# Pros_touch_weight_sensor-v1_0_0-2023-4-8.net
KiCad netlist of a schematic drawn in EasyEDA Pro
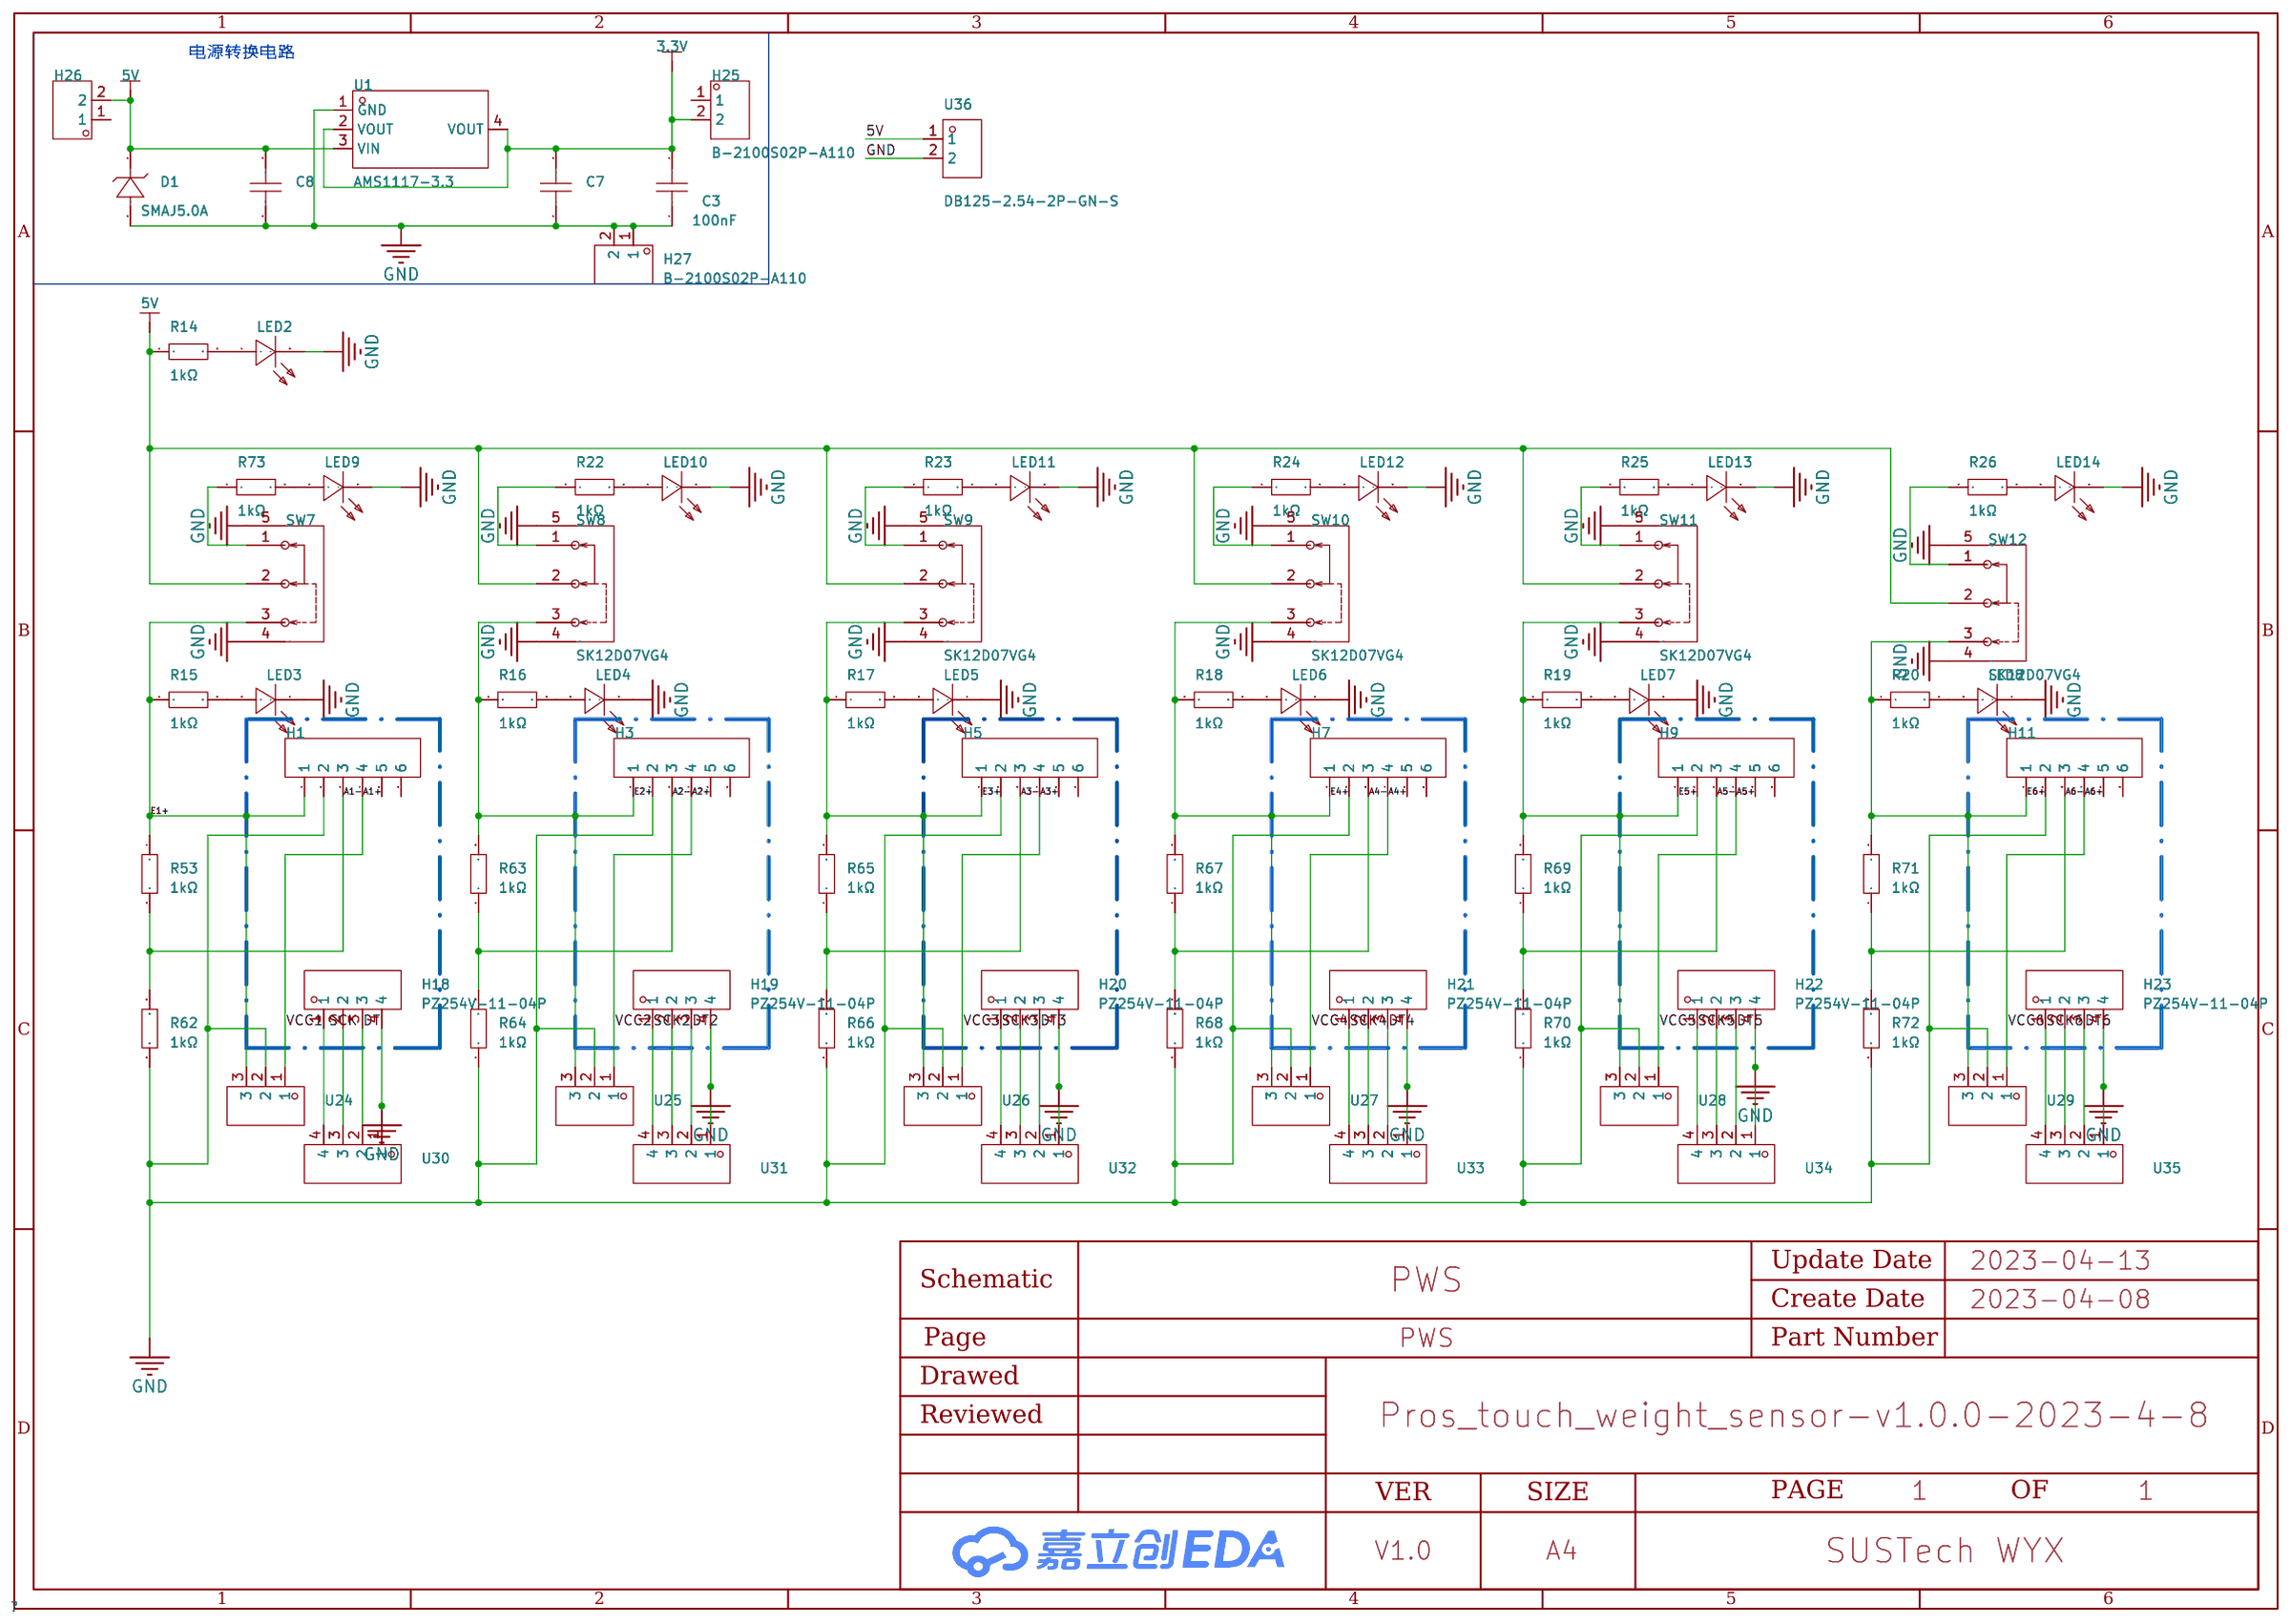
[diagram p0: schematic sheet]

(export (version "E")
  (design (tool "Eeschema 10.0.6"))
  (components
    (comp (ref "C3")
      (value "100nF")
      (footprint "easyedapro:C0603")
      (description "容值:100nF;精度:±10%;额定电压:50V;材质(温度系数):X7R;")
      (fields
        (field (name "Manufacturer Part") "CC0603KRX7R9BB104")
        (field (name "Manufacturer") "YAGEO(国巨)")
      )
      (libsource (lib "easyedapro") (part "CC0603KRX7R9BB104"))
    )
    (comp (ref "C7")
      (value "GRM31CC80J476KE01L")
      (footprint "easyedapro:C1206")
      (fields (field (name "Manufacturer") "muRata(村田)"))
      (libsource (lib "easyedapro") (part "GRM31CC80J476KE01L"))
    )
    (comp (ref "C8")
      (value "GRM31CC80J476KE01L")
      (footprint "easyedapro:C1206")
      (fields (field (name "Manufacturer") "muRata(村田)"))
      (libsource (lib "easyedapro") (part "GRM31CC80J476KE01L"))
    )
    (comp (ref "D1")
      (value "SMAJ5.0A")
      (footprint "easyedapro:SMA_L4.3-W2.6-LS5.0-RD")
      (fields (field (name "Manufacturer") "FUXINSEMI(富芯森美)"))
      (libsource (lib "easyedapro") (part "SMAJ5.0A_C908198"))
    )
    (comp (ref "H1")
      (value "2.54-1x6P直针")
      (footprint "easyedapro:HDR-TH_6P-P2.54-V-M-1")
      (fields (field (name "Manufacturer") "BOOMELE(博穆精密)"))
      (libsource (lib "easyedapro") (part "Header-Male-2.54_1x6"))
    )
    (comp (ref "H3")
      (value "2.54-1x6P直针")
      (footprint "easyedapro:HDR-TH_6P-P2.54-V-M-1")
      (fields (field (name "Manufacturer") "BOOMELE(博穆精密)"))
      (libsource (lib "easyedapro") (part "Header-Male-2.54_1x6"))
    )
    (comp (ref "H5")
      (value "2.54-1x6P直针")
      (footprint "easyedapro:HDR-TH_6P-P2.54-V-M-1")
      (fields (field (name "Manufacturer") "BOOMELE(博穆精密)"))
      (libsource (lib "easyedapro") (part "Header-Male-2.54_1x6"))
    )
    (comp (ref "H7")
      (value "2.54-1x6P直针")
      (footprint "easyedapro:HDR-TH_6P-P2.54-V-M-1")
      (fields (field (name "Manufacturer") "BOOMELE(博穆精密)"))
      (libsource (lib "easyedapro") (part "Header-Male-2.54_1x6"))
    )
    (comp (ref "H9")
      (value "2.54-1x6P直针")
      (footprint "easyedapro:HDR-TH_6P-P2.54-V-M-1")
      (fields (field (name "Manufacturer") "BOOMELE(博穆精密)"))
      (libsource (lib "easyedapro") (part "Header-Male-2.54_1x6"))
    )
    (comp (ref "H11")
      (value "2.54-1x6P直针")
      (footprint "easyedapro:HDR-TH_6P-P2.54-V-M-1")
      (fields (field (name "Manufacturer") "BOOMELE(博穆精密)"))
      (libsource (lib "easyedapro") (part "Header-Male-2.54_1x6"))
    )
    (comp (ref "H18")
      (value "PZ254V-11-04P")
      (footprint "easyedapro:HDR-TH_4P-P2.54-V-M")
      (fields (field (name "Manufacturer") "XFCN(兴飞)"))
      (libsource (lib "easyedapro") (part "PZ254V-11-04P_C2691448"))
    )
    (comp (ref "H19")
      (value "PZ254V-11-04P")
      (footprint "easyedapro:HDR-TH_4P-P2.54-V-M")
      (fields (field (name "Manufacturer") "XFCN(兴飞)"))
      (libsource (lib "easyedapro") (part "PZ254V-11-04P_C2691448"))
    )
    (comp (ref "H20")
      (value "PZ254V-11-04P")
      (footprint "easyedapro:HDR-TH_4P-P2.54-V-M")
      (fields (field (name "Manufacturer") "XFCN(兴飞)"))
      (libsource (lib "easyedapro") (part "PZ254V-11-04P_C2691448"))
    )
    (comp (ref "H21")
      (value "PZ254V-11-04P")
      (footprint "easyedapro:HDR-TH_4P-P2.54-V-M")
      (fields (field (name "Manufacturer") "XFCN(兴飞)"))
      (libsource (lib "easyedapro") (part "PZ254V-11-04P_C2691448"))
    )
    (comp (ref "H22")
      (value "PZ254V-11-04P")
      (footprint "easyedapro:HDR-TH_4P-P2.54-V-M")
      (fields (field (name "Manufacturer") "XFCN(兴飞)"))
      (libsource (lib "easyedapro") (part "PZ254V-11-04P_C2691448"))
    )
    (comp (ref "H23")
      (value "PZ254V-11-04P")
      (footprint "easyedapro:HDR-TH_4P-P2.54-V-M")
      (fields (field (name "Manufacturer") "XFCN(兴飞)"))
      (libsource (lib "easyedapro") (part "PZ254V-11-04P_C2691448"))
    )
    (comp (ref "H25")
      (value "B-2100S02P-A110")
      (footprint "easyedapro:HDR-TH_2P-P2.54-V-M-1")
      (fields (field (name "Manufacturer") "Ckmtw(灿科盟)"))
      (libsource (lib "easyedapro") (part "210S-1*2P L=11.6MMGold-plated black"))
    )
    (comp (ref "H26")
      (value "B-2100S02P-A110")
      (footprint "easyedapro:HDR-TH_2P-P2.54-V-M-1")
      (fields (field (name "Manufacturer") "Ckmtw(灿科盟)"))
      (libsource (lib "easyedapro") (part "210S-1*2P L=11.6MMGold-plated black"))
    )
    (comp (ref "H27")
      (value "B-2100S02P-A110")
      (footprint "easyedapro:HDR-TH_2P-P2.54-V-M-1")
      (fields (field (name "Manufacturer") "Ckmtw(灿科盟)"))
      (libsource (lib "easyedapro") (part "210S-1*2P L=11.6MMGold-plated black"))
    )
    (comp (ref "LED2")
      (value "NCD0805B2")
      (footprint "easyedapro:LED0805-RD")
      (description "照明颜色:蓝色;主波长/色坐标:468~478nm;")
      (fields (field (name "Manufacturer") "国星光电"))
      (libsource (lib "easyedapro") (part "FC-A2012BK-470H2"))
    )
    (comp (ref "LED3")
      (value "NCD1206G1")
      (footprint "easyedapro:LED1206-RD")
      (description "照明颜色:翠绿;色温 - CCT（K）:-;主波长/色坐标:525~530nm;")
      (fields (field (name "Manufacturer") "国星光电"))
      (libsource (lib "easyedapro") (part "FC-3215UGK-520D"))
    )
    (comp (ref "LED4")
      (value "NCD1206G1")
      (footprint "easyedapro:LED1206-RD")
      (description "照明颜色:翠绿;色温 - CCT（K）:-;主波长/色坐标:525~530nm;")
      (fields (field (name "Manufacturer") "国星光电"))
      (libsource (lib "easyedapro") (part "FC-3215UGK-520D"))
    )
    (comp (ref "LED5")
      (value "NCD1206G1")
      (footprint "easyedapro:LED1206-RD")
      (description "照明颜色:翠绿;色温 - CCT（K）:-;主波长/色坐标:525~530nm;")
      (fields (field (name "Manufacturer") "国星光电"))
      (libsource (lib "easyedapro") (part "FC-3215UGK-520D"))
    )
    (comp (ref "LED6")
      (value "NCD1206G1")
      (footprint "easyedapro:LED1206-RD")
      (description "照明颜色:翠绿;色温 - CCT（K）:-;主波长/色坐标:525~530nm;")
      (fields (field (name "Manufacturer") "国星光电"))
      (libsource (lib "easyedapro") (part "FC-3215UGK-520D"))
    )
    (comp (ref "LED7")
      (value "NCD1206G1")
      (footprint "easyedapro:LED1206-RD")
      (description "照明颜色:翠绿;色温 - CCT（K）:-;主波长/色坐标:525~530nm;")
      (fields (field (name "Manufacturer") "国星光电"))
      (libsource (lib "easyedapro") (part "FC-3215UGK-520D"))
    )
    (comp (ref "LED8")
      (value "NCD1206G1")
      (footprint "easyedapro:LED1206-RD")
      (description "照明颜色:翠绿;色温 - CCT（K）:-;主波长/色坐标:525~530nm;")
      (fields (field (name "Manufacturer") "国星光电"))
      (libsource (lib "easyedapro") (part "FC-3215UGK-520D"))
    )
    (comp (ref "LED9")
      (value "NCD0805B2")
      (footprint "easyedapro:LED0805-RD")
      (description "照明颜色:蓝色;主波长/色坐标:468~478nm;")
      (fields (field (name "Manufacturer") "国星光电"))
      (libsource (lib "easyedapro") (part "FC-A2012BK-470H2"))
    )
    (comp (ref "LED10")
      (value "NCD0805B2")
      (footprint "easyedapro:LED0805-RD")
      (description "照明颜色:蓝色;主波长/色坐标:468~478nm;")
      (fields (field (name "Manufacturer") "国星光电"))
      (libsource (lib "easyedapro") (part "FC-A2012BK-470H2"))
    )
    (comp (ref "LED11")
      (value "NCD0805B2")
      (footprint "easyedapro:LED0805-RD")
      (description "照明颜色:蓝色;主波长/色坐标:468~478nm;")
      (fields (field (name "Manufacturer") "国星光电"))
      (libsource (lib "easyedapro") (part "FC-A2012BK-470H2"))
    )
    (comp (ref "LED12")
      (value "NCD0805B2")
      (footprint "easyedapro:LED0805-RD")
      (description "照明颜色:蓝色;主波长/色坐标:468~478nm;")
      (fields (field (name "Manufacturer") "国星光电"))
      (libsource (lib "easyedapro") (part "FC-A2012BK-470H2"))
    )
    (comp (ref "LED13")
      (value "NCD0805B2")
      (footprint "easyedapro:LED0805-RD")
      (description "照明颜色:蓝色;主波长/色坐标:468~478nm;")
      (fields (field (name "Manufacturer") "国星光电"))
      (libsource (lib "easyedapro") (part "FC-A2012BK-470H2"))
    )
    (comp (ref "LED14")
      (value "NCD0805B2")
      (footprint "easyedapro:LED0805-RD")
      (description "照明颜色:蓝色;主波长/色坐标:468~478nm;")
      (fields (field (name "Manufacturer") "国星光电"))
      (libsource (lib "easyedapro") (part "FC-A2012BK-470H2"))
    )
    (comp (ref "R14")
      (value "1kΩ")
      (footprint "easyedapro:R0603")
      (description "电阻类型:厚膜电阻;阻值:1kΩ;精度:±1%;功率:1/10W;温度系数:±100ppm/°C;最大工作电压:75V;工作温度范围:-55°C~+155°C;")
      (fields
        (field (name "Manufacturer Part") "0603WAF1001T5E")
        (field (name "Manufacturer") "UNI-ROYAL(厚声)")
      )
      (libsource (lib "easyedapro") (part "0603WAF1001T5E"))
    )
    (comp (ref "R15")
      (value "1kΩ")
      (footprint "easyedapro:R0603")
      (description "电阻类型:厚膜电阻;阻值:1kΩ;精度:±1%;功率:1/10W;温度系数:±100ppm/°C;最大工作电压:75V;工作温度范围:-55°C~+155°C;")
      (fields
        (field (name "Manufacturer Part") "0603WAF1001T5E")
        (field (name "Manufacturer") "UNI-ROYAL(厚声)")
      )
      (libsource (lib "easyedapro") (part "0603WAF1001T5E"))
    )
    (comp (ref "R16")
      (value "1kΩ")
      (footprint "easyedapro:R0603")
      (description "电阻类型:厚膜电阻;阻值:1kΩ;精度:±1%;功率:1/10W;温度系数:±100ppm/°C;最大工作电压:75V;工作温度范围:-55°C~+155°C;")
      (fields
        (field (name "Manufacturer Part") "0603WAF1001T5E")
        (field (name "Manufacturer") "UNI-ROYAL(厚声)")
      )
      (libsource (lib "easyedapro") (part "0603WAF1001T5E"))
    )
    (comp (ref "R17")
      (value "1kΩ")
      (footprint "easyedapro:R0603")
      (description "电阻类型:厚膜电阻;阻值:1kΩ;精度:±1%;功率:1/10W;温度系数:±100ppm/°C;最大工作电压:75V;工作温度范围:-55°C~+155°C;")
      (fields
        (field (name "Manufacturer Part") "0603WAF1001T5E")
        (field (name "Manufacturer") "UNI-ROYAL(厚声)")
      )
      (libsource (lib "easyedapro") (part "0603WAF1001T5E"))
    )
    (comp (ref "R18")
      (value "1kΩ")
      (footprint "easyedapro:R0603")
      (description "电阻类型:厚膜电阻;阻值:1kΩ;精度:±1%;功率:1/10W;温度系数:±100ppm/°C;最大工作电压:75V;工作温度范围:-55°C~+155°C;")
      (fields
        (field (name "Manufacturer Part") "0603WAF1001T5E")
        (field (name "Manufacturer") "UNI-ROYAL(厚声)")
      )
      (libsource (lib "easyedapro") (part "0603WAF1001T5E"))
    )
    (comp (ref "R19")
      (value "1kΩ")
      (footprint "easyedapro:R0603")
      (description "电阻类型:厚膜电阻;阻值:1kΩ;精度:±1%;功率:1/10W;温度系数:±100ppm/°C;最大工作电压:75V;工作温度范围:-55°C~+155°C;")
      (fields
        (field (name "Manufacturer Part") "0603WAF1001T5E")
        (field (name "Manufacturer") "UNI-ROYAL(厚声)")
      )
      (libsource (lib "easyedapro") (part "0603WAF1001T5E"))
    )
    (comp (ref "R20")
      (value "1kΩ")
      (footprint "easyedapro:R0603")
      (description "电阻类型:厚膜电阻;阻值:1kΩ;精度:±1%;功率:1/10W;温度系数:±100ppm/°C;最大工作电压:75V;工作温度范围:-55°C~+155°C;")
      (fields
        (field (name "Manufacturer Part") "0603WAF1001T5E")
        (field (name "Manufacturer") "UNI-ROYAL(厚声)")
      )
      (libsource (lib "easyedapro") (part "0603WAF1001T5E"))
    )
    (comp (ref "R22")
      (value "1kΩ")
      (footprint "easyedapro:R0603")
      (description "电阻类型:厚膜电阻;阻值:1kΩ;精度:±1%;功率:1/10W;温度系数:±100ppm/°C;最大工作电压:75V;工作温度范围:-55°C~+155°C;")
      (fields
        (field (name "Manufacturer Part") "0603WAF1001T5E")
        (field (name "Manufacturer") "UNI-ROYAL(厚声)")
      )
      (libsource (lib "easyedapro") (part "0603WAF1001T5E"))
    )
    (comp (ref "R23")
      (value "1kΩ")
      (footprint "easyedapro:R0603")
      (description "电阻类型:厚膜电阻;阻值:1kΩ;精度:±1%;功率:1/10W;温度系数:±100ppm/°C;最大工作电压:75V;工作温度范围:-55°C~+155°C;")
      (fields
        (field (name "Manufacturer Part") "0603WAF1001T5E")
        (field (name "Manufacturer") "UNI-ROYAL(厚声)")
      )
      (libsource (lib "easyedapro") (part "0603WAF1001T5E"))
    )
    (comp (ref "R24")
      (value "1kΩ")
      (footprint "easyedapro:R0603")
      (description "电阻类型:厚膜电阻;阻值:1kΩ;精度:±1%;功率:1/10W;温度系数:±100ppm/°C;最大工作电压:75V;工作温度范围:-55°C~+155°C;")
      (fields
        (field (name "Manufacturer Part") "0603WAF1001T5E")
        (field (name "Manufacturer") "UNI-ROYAL(厚声)")
      )
      (libsource (lib "easyedapro") (part "0603WAF1001T5E"))
    )
    (comp (ref "R25")
      (value "1kΩ")
      (footprint "easyedapro:R0603")
      (description "电阻类型:厚膜电阻;阻值:1kΩ;精度:±1%;功率:1/10W;温度系数:±100ppm/°C;最大工作电压:75V;工作温度范围:-55°C~+155°C;")
      (fields
        (field (name "Manufacturer Part") "0603WAF1001T5E")
        (field (name "Manufacturer") "UNI-ROYAL(厚声)")
      )
      (libsource (lib "easyedapro") (part "0603WAF1001T5E"))
    )
    (comp (ref "R26")
      (value "1kΩ")
      (footprint "easyedapro:R0603")
      (description "电阻类型:厚膜电阻;阻值:1kΩ;精度:±1%;功率:1/10W;温度系数:±100ppm/°C;最大工作电压:75V;工作温度范围:-55°C~+155°C;")
      (fields
        (field (name "Manufacturer Part") "0603WAF1001T5E")
        (field (name "Manufacturer") "UNI-ROYAL(厚声)")
      )
      (libsource (lib "easyedapro") (part "0603WAF1001T5E"))
    )
    (comp (ref "R53")
      (value "1kΩ")
      (footprint "easyedapro:R0402")
      (description "电阻类型:薄膜电阻;阻值:1kΩ;精度:±0.1%;功率:63mW;温度系数:±25ppm/K;最大工作电压:50V;工作温度范围:-55°C~+155°C;")
      (fields (field (name "Manufacturer Part") "ERA2AEB102X") (field (name "Manufacturer") "PANASONIC(松下)"))
      (libsource (lib "easyedapro") (part "ERA2AEB102X"))
    )
    (comp (ref "R62")
      (value "1kΩ")
      (footprint "easyedapro:R0402")
      (description "电阻类型:薄膜电阻;阻值:1kΩ;精度:±0.1%;功率:63mW;温度系数:±25ppm/K;最大工作电压:50V;工作温度范围:-55°C~+155°C;")
      (fields (field (name "Manufacturer Part") "ERA2AEB102X") (field (name "Manufacturer") "PANASONIC(松下)"))
      (libsource (lib "easyedapro") (part "ERA2AEB102X"))
    )
    (comp (ref "R63")
      (value "1kΩ")
      (footprint "easyedapro:R0402")
      (description "电阻类型:薄膜电阻;阻值:1kΩ;精度:±0.1%;功率:63mW;温度系数:±25ppm/K;最大工作电压:50V;工作温度范围:-55°C~+155°C;")
      (fields (field (name "Manufacturer Part") "ERA2AEB102X") (field (name "Manufacturer") "PANASONIC(松下)"))
      (libsource (lib "easyedapro") (part "ERA2AEB102X"))
    )
    (comp (ref "R64")
      (value "1kΩ")
      (footprint "easyedapro:R0402")
      (description "电阻类型:薄膜电阻;阻值:1kΩ;精度:±0.1%;功率:63mW;温度系数:±25ppm/K;最大工作电压:50V;工作温度范围:-55°C~+155°C;")
      (fields (field (name "Manufacturer Part") "ERA2AEB102X") (field (name "Manufacturer") "PANASONIC(松下)"))
      (libsource (lib "easyedapro") (part "ERA2AEB102X"))
    )
    (comp (ref "R65")
      (value "1kΩ")
      (footprint "easyedapro:R0402")
      (description "电阻类型:薄膜电阻;阻值:1kΩ;精度:±0.1%;功率:63mW;温度系数:±25ppm/K;最大工作电压:50V;工作温度范围:-55°C~+155°C;")
      (fields (field (name "Manufacturer Part") "ERA2AEB102X") (field (name "Manufacturer") "PANASONIC(松下)"))
      (libsource (lib "easyedapro") (part "ERA2AEB102X"))
    )
    (comp (ref "R66")
      (value "1kΩ")
      (footprint "easyedapro:R0402")
      (description "电阻类型:薄膜电阻;阻值:1kΩ;精度:±0.1%;功率:63mW;温度系数:±25ppm/K;最大工作电压:50V;工作温度范围:-55°C~+155°C;")
      (fields (field (name "Manufacturer Part") "ERA2AEB102X") (field (name "Manufacturer") "PANASONIC(松下)"))
      (libsource (lib "easyedapro") (part "ERA2AEB102X"))
    )
    (comp (ref "R67")
      (value "1kΩ")
      (footprint "easyedapro:R0402")
      (description "电阻类型:薄膜电阻;阻值:1kΩ;精度:±0.1%;功率:63mW;温度系数:±25ppm/K;最大工作电压:50V;工作温度范围:-55°C~+155°C;")
      (fields (field (name "Manufacturer Part") "ERA2AEB102X") (field (name "Manufacturer") "PANASONIC(松下)"))
      (libsource (lib "easyedapro") (part "ERA2AEB102X"))
    )
    (comp (ref "R68")
      (value "1kΩ")
      (footprint "easyedapro:R0402")
      (description "电阻类型:薄膜电阻;阻值:1kΩ;精度:±0.1%;功率:63mW;温度系数:±25ppm/K;最大工作电压:50V;工作温度范围:-55°C~+155°C;")
      (fields (field (name "Manufacturer Part") "ERA2AEB102X") (field (name "Manufacturer") "PANASONIC(松下)"))
      (libsource (lib "easyedapro") (part "ERA2AEB102X"))
    )
    (comp (ref "R69")
      (value "1kΩ")
      (footprint "easyedapro:R0402")
      (description "电阻类型:薄膜电阻;阻值:1kΩ;精度:±0.1%;功率:63mW;温度系数:±25ppm/K;最大工作电压:50V;工作温度范围:-55°C~+155°C;")
      (fields (field (name "Manufacturer Part") "ERA2AEB102X") (field (name "Manufacturer") "PANASONIC(松下)"))
      (libsource (lib "easyedapro") (part "ERA2AEB102X"))
    )
    (comp (ref "R70")
      (value "1kΩ")
      (footprint "easyedapro:R0402")
      (description "电阻类型:薄膜电阻;阻值:1kΩ;精度:±0.1%;功率:63mW;温度系数:±25ppm/K;最大工作电压:50V;工作温度范围:-55°C~+155°C;")
      (fields (field (name "Manufacturer Part") "ERA2AEB102X") (field (name "Manufacturer") "PANASONIC(松下)"))
      (libsource (lib "easyedapro") (part "ERA2AEB102X"))
    )
    (comp (ref "R71")
      (value "1kΩ")
      (footprint "easyedapro:R0402")
      (description "电阻类型:薄膜电阻;阻值:1kΩ;精度:±0.1%;功率:63mW;温度系数:±25ppm/K;最大工作电压:50V;工作温度范围:-55°C~+155°C;")
      (fields (field (name "Manufacturer Part") "ERA2AEB102X") (field (name "Manufacturer") "PANASONIC(松下)"))
      (libsource (lib "easyedapro") (part "ERA2AEB102X"))
    )
    (comp (ref "R72")
      (value "1kΩ")
      (footprint "easyedapro:R0402")
      (description "电阻类型:薄膜电阻;阻值:1kΩ;精度:±0.1%;功率:63mW;温度系数:±25ppm/K;最大工作电压:50V;工作温度范围:-55°C~+155°C;")
      (fields (field (name "Manufacturer Part") "ERA2AEB102X") (field (name "Manufacturer") "PANASONIC(松下)"))
      (libsource (lib "easyedapro") (part "ERA2AEB102X"))
    )
    (comp (ref "R73")
      (value "1kΩ")
      (footprint "easyedapro:R0603")
      (description "电阻类型:厚膜电阻;阻值:1kΩ;精度:±1%;功率:1/10W;温度系数:±100ppm/°C;最大工作电压:75V;工作温度范围:-55°C~+155°C;")
      (fields
        (field (name "Manufacturer Part") "0603WAF1001T5E")
        (field (name "Manufacturer") "UNI-ROYAL(厚声)")
      )
      (libsource (lib "easyedapro") (part "0603WAF1001T5E"))
    )
    (comp (ref "SW7")
      (value "SK12D07VG4")
      (footprint "easyedapro:SW-TH_SK12D07VG4")
      (description "额定电压 DC:50V;触点额定电流:500mA @ 50VDC;电路结构:SPDT;额定电压 AC:-;开关功能:On-On;")
      (fields (field (name "Manufacturer") "SHOU HAN(首韩)"))
      (libsource (lib "easyedapro") (part "SK12D07VG4"))
    )
    (comp (ref "SW8")
      (value "SK12D07VG4")
      (footprint "easyedapro:SW-TH_SK12D07VG4")
      (description "额定电压 DC:50V;触点额定电流:500mA @ 50VDC;电路结构:SPDT;额定电压 AC:-;开关功能:On-On;")
      (fields (field (name "Manufacturer") "SHOU HAN(首韩)"))
      (libsource (lib "easyedapro") (part "SK12D07VG4"))
    )
    (comp (ref "SW9")
      (value "SK12D07VG4")
      (footprint "easyedapro:SW-TH_SK12D07VG4")
      (description "额定电压 DC:50V;触点额定电流:500mA @ 50VDC;电路结构:SPDT;额定电压 AC:-;开关功能:On-On;")
      (fields (field (name "Manufacturer") "SHOU HAN(首韩)"))
      (libsource (lib "easyedapro") (part "SK12D07VG4"))
    )
    (comp (ref "SW10")
      (value "SK12D07VG4")
      (footprint "easyedapro:SW-TH_SK12D07VG4")
      (description "额定电压 DC:50V;触点额定电流:500mA @ 50VDC;电路结构:SPDT;额定电压 AC:-;开关功能:On-On;")
      (fields (field (name "Manufacturer") "SHOU HAN(首韩)"))
      (libsource (lib "easyedapro") (part "SK12D07VG4"))
    )
    (comp (ref "SW11")
      (value "SK12D07VG4")
      (footprint "easyedapro:SW-TH_SK12D07VG4")
      (description "额定电压 DC:50V;触点额定电流:500mA @ 50VDC;电路结构:SPDT;额定电压 AC:-;开关功能:On-On;")
      (fields (field (name "Manufacturer") "SHOU HAN(首韩)"))
      (libsource (lib "easyedapro") (part "SK12D07VG4"))
    )
    (comp (ref "SW12")
      (value "SK12D07VG4")
      (footprint "easyedapro:SW-TH_SK12D07VG4")
      (description "额定电压 DC:50V;触点额定电流:500mA @ 50VDC;电路结构:SPDT;额定电压 AC:-;开关功能:On-On;")
      (fields (field (name "Manufacturer") "SHOU HAN(首韩)"))
      (libsource (lib "easyedapro") (part "SK12D07VG4"))
    )
    (comp (ref "U1")
      (value "AMS1117-3.3")
      (footprint "easyedapro:SOT-223-3_L6.5-W3.4-P2.30-LS7.0-BR")
      (description "输出类型:固定;输出极性:正;最大输入电压:-;输出电压:3.3V;输出电流:1A;电源纹波抑制比(PSRR):72dB@(120Hz);")
      (fields (field (name "Manufacturer") "AMS"))
      (libsource (lib "easyedapro") (part "AMS1117-3.3"))
    )
    (comp (ref "U24")
      (value "DB125-2.54-3P-GN-S")
      (footprint "easyedapro:CONN-TH_DB125-2.54-3P-GN")
      (fields (field (name "Manufacturer") "DIBO(地博电气)"))
      (libsource (lib "easyedapro") (part "DB125-2.54-3P-GN"))
    )
    (comp (ref "U25")
      (value "DB125-2.54-3P-GN-S")
      (footprint "easyedapro:CONN-TH_DB125-2.54-3P-GN")
      (fields (field (name "Manufacturer") "DIBO(地博电气)"))
      (libsource (lib "easyedapro") (part "DB125-2.54-3P-GN"))
    )
    (comp (ref "U26")
      (value "DB125-2.54-3P-GN-S")
      (footprint "easyedapro:CONN-TH_DB125-2.54-3P-GN")
      (fields (field (name "Manufacturer") "DIBO(地博电气)"))
      (libsource (lib "easyedapro") (part "DB125-2.54-3P-GN"))
    )
    (comp (ref "U27")
      (value "DB125-2.54-3P-GN-S")
      (footprint "easyedapro:CONN-TH_DB125-2.54-3P-GN")
      (fields (field (name "Manufacturer") "DIBO(地博电气)"))
      (libsource (lib "easyedapro") (part "DB125-2.54-3P-GN"))
    )
    (comp (ref "U28")
      (value "DB125-2.54-3P-GN-S")
      (footprint "easyedapro:CONN-TH_DB125-2.54-3P-GN")
      (fields (field (name "Manufacturer") "DIBO(地博电气)"))
      (libsource (lib "easyedapro") (part "DB125-2.54-3P-GN"))
    )
    (comp (ref "U29")
      (value "DB125-2.54-3P-GN-S")
      (footprint "easyedapro:CONN-TH_DB125-2.54-3P-GN")
      (fields (field (name "Manufacturer") "DIBO(地博电气)"))
      (libsource (lib "easyedapro") (part "DB125-2.54-3P-GN"))
    )
    (comp (ref "U30")
      (value "DB125-2.54-4P-GN-S")
      (footprint "easyedapro:CONN-TH_DB125-2.54-4P-GN")
      (fields (field (name "Manufacturer") "DIBO(地博电气)"))
      (libsource (lib "easyedapro") (part "DB125-2.54-4P-GN"))
    )
    (comp (ref "U31")
      (value "DB125-2.54-4P-GN-S")
      (footprint "easyedapro:CONN-TH_DB125-2.54-4P-GN")
      (fields (field (name "Manufacturer") "DIBO(地博电气)"))
      (libsource (lib "easyedapro") (part "DB125-2.54-4P-GN"))
    )
    (comp (ref "U32")
      (value "DB125-2.54-4P-GN-S")
      (footprint "easyedapro:CONN-TH_DB125-2.54-4P-GN")
      (fields (field (name "Manufacturer") "DIBO(地博电气)"))
      (libsource (lib "easyedapro") (part "DB125-2.54-4P-GN"))
    )
    (comp (ref "U33")
      (value "DB125-2.54-4P-GN-S")
      (footprint "easyedapro:CONN-TH_DB125-2.54-4P-GN")
      (fields (field (name "Manufacturer") "DIBO(地博电气)"))
      (libsource (lib "easyedapro") (part "DB125-2.54-4P-GN"))
    )
    (comp (ref "U34")
      (value "DB125-2.54-4P-GN-S")
      (footprint "easyedapro:CONN-TH_DB125-2.54-4P-GN")
      (fields (field (name "Manufacturer") "DIBO(地博电气)"))
      (libsource (lib "easyedapro") (part "DB125-2.54-4P-GN"))
    )
    (comp (ref "U35")
      (value "DB125-2.54-4P-GN-S")
      (footprint "easyedapro:CONN-TH_DB125-2.54-4P-GN")
      (fields (field (name "Manufacturer") "DIBO(地博电气)"))
      (libsource (lib "easyedapro") (part "DB125-2.54-4P-GN"))
    )
    (comp (ref "U36")
      (value "DB125-2.54-2P-GN-S")
      (footprint "easyedapro:CONN-TH_DB125-2.54-2P-GN")
      (fields (field (name "Manufacturer") "DIBO(地博电气)"))
      (libsource (lib "easyedapro") (part "DB125-2.54-2P-GN"))
    )
  )
  (nets
    (net (code "1") (name "/A1+") (class "Default")
      (node (ref "H1") (pin "4") (pinfunction "4_4") (pintype "input"))
      (node (ref "U24") (pin "1") (pinfunction "1_1") (pintype "input"))
    )
    (net (code "2") (name "/A1-") (class "Default")
      (node (ref "H1") (pin "3") (pinfunction "3_3") (pintype "input"))
      (node (ref "R53") (pin "2") (pinfunction "2_2") (pintype "input"))
      (node (ref "R62") (pin "2") (pinfunction "2_2") (pintype "input"))
    )
    (net (code "3") (name "/A2+") (class "Default")
      (node (ref "H3") (pin "4") (pinfunction "4_4") (pintype "input"))
      (node (ref "U25") (pin "1") (pinfunction "1_1") (pintype "input"))
    )
    (net (code "4") (name "/A2-") (class "Default")
      (node (ref "H3") (pin "3") (pinfunction "3_3") (pintype "input"))
      (node (ref "R63") (pin "1") (pinfunction "1_1") (pintype "input"))
      (node (ref "R64") (pin "2") (pinfunction "2_2") (pintype "input"))
    )
    (net (code "5") (name "/A3+") (class "Default")
      (node (ref "H5") (pin "4") (pinfunction "4_4") (pintype "input"))
      (node (ref "U26") (pin "1") (pinfunction "1_1") (pintype "input"))
    )
    (net (code "6") (name "/A3-") (class "Default")
      (node (ref "H5") (pin "3") (pinfunction "3_3") (pintype "input"))
      (node (ref "R65") (pin "1") (pinfunction "1_1") (pintype "input"))
      (node (ref "R66") (pin "2") (pinfunction "2_2") (pintype "input"))
    )
    (net (code "7") (name "/A4+") (class "Default")
      (node (ref "H7") (pin "4") (pinfunction "4_4") (pintype "input"))
      (node (ref "U27") (pin "1") (pinfunction "1_1") (pintype "input"))
    )
    (net (code "8") (name "/A4-") (class "Default")
      (node (ref "H7") (pin "3") (pinfunction "3_3") (pintype "input"))
      (node (ref "R67") (pin "1") (pinfunction "1_1") (pintype "input"))
      (node (ref "R68") (pin "2") (pinfunction "2_2") (pintype "input"))
    )
    (net (code "9") (name "/A5+") (class "Default")
      (node (ref "H9") (pin "4") (pinfunction "4_4") (pintype "input"))
      (node (ref "U28") (pin "1") (pinfunction "1_1") (pintype "input"))
    )
    (net (code "10") (name "/A5-") (class "Default")
      (node (ref "H9") (pin "3") (pinfunction "3_3") (pintype "input"))
      (node (ref "R69") (pin "1") (pinfunction "1_1") (pintype "input"))
      (node (ref "R70") (pin "2") (pinfunction "2_2") (pintype "input"))
    )
    (net (code "11") (name "/A6+") (class "Default")
      (node (ref "H11") (pin "4") (pinfunction "4_4") (pintype "input"))
      (node (ref "U29") (pin "1") (pinfunction "1_1") (pintype "input"))
    )
    (net (code "12") (name "/A6-") (class "Default")
      (node (ref "H11") (pin "3") (pinfunction "3_3") (pintype "input"))
      (node (ref "R71") (pin "1") (pinfunction "1_1") (pintype "input"))
      (node (ref "R72") (pin "2") (pinfunction "2_2") (pintype "input"))
    )
    (net (code "13") (name "/DT") (class "Default")
      (node (ref "H18") (pin "3") (pinfunction "3_3") (pintype "input"))
      (node (ref "U30") (pin "2") (pinfunction "2_2") (pintype "input"))
    )
    (net (code "14") (name "/DT2") (class "Default")
      (node (ref "H19") (pin "3") (pinfunction "3_3") (pintype "input"))
      (node (ref "U31") (pin "2") (pinfunction "2_2") (pintype "input"))
    )
    (net (code "15") (name "/DT3") (class "Default")
      (node (ref "H20") (pin "3") (pinfunction "3_3") (pintype "input"))
      (node (ref "U32") (pin "2") (pinfunction "2_2") (pintype "input"))
    )
    (net (code "16") (name "/DT4") (class "Default")
      (node (ref "H21") (pin "3") (pinfunction "3_3") (pintype "input"))
      (node (ref "U33") (pin "2") (pinfunction "2_2") (pintype "input"))
    )
    (net (code "17") (name "/DT5") (class "Default")
      (node (ref "H22") (pin "3") (pinfunction "3_3") (pintype "input"))
      (node (ref "U34") (pin "2") (pinfunction "2_2") (pintype "input"))
    )
    (net (code "18") (name "/DT6") (class "Default")
      (node (ref "H23") (pin "3") (pinfunction "3_3") (pintype "input"))
      (node (ref "U35") (pin "2") (pinfunction "2_2") (pintype "input"))
    )
    (net (code "19") (name "/E1+") (class "Default")
      (node (ref "H1") (pin "1") (pinfunction "1_1") (pintype "input"))
      (node (ref "R15") (pin "1") (pinfunction "1_1") (pintype "input"))
      (node (ref "R53") (pin "1") (pinfunction "1_1") (pintype "input"))
      (node (ref "SW7") (pin "3") (pinfunction "3_3") (pintype "input"))
      (node (ref "U24") (pin "3") (pinfunction "3_3") (pintype "input"))
    )
    (net (code "20") (name "/E2+") (class "Default")
      (node (ref "H3") (pin "1") (pinfunction "1_1") (pintype "input"))
      (node (ref "R16") (pin "1") (pinfunction "1_1") (pintype "input"))
      (node (ref "R63") (pin "2") (pinfunction "2_2") (pintype "input"))
      (node (ref "SW8") (pin "3") (pinfunction "3_3") (pintype "input"))
      (node (ref "U25") (pin "3") (pinfunction "3_3") (pintype "input"))
    )
    (net (code "21") (name "/E3+") (class "Default")
      (node (ref "H5") (pin "1") (pinfunction "1_1") (pintype "input"))
      (node (ref "R17") (pin "1") (pinfunction "1_1") (pintype "input"))
      (node (ref "R65") (pin "2") (pinfunction "2_2") (pintype "input"))
      (node (ref "SW9") (pin "3") (pinfunction "3_3") (pintype "input"))
      (node (ref "U26") (pin "3") (pinfunction "3_3") (pintype "input"))
    )
    (net (code "22") (name "/E4+") (class "Default")
      (node (ref "H7") (pin "1") (pinfunction "1_1") (pintype "input"))
      (node (ref "R18") (pin "1") (pinfunction "1_1") (pintype "input"))
      (node (ref "R67") (pin "2") (pinfunction "2_2") (pintype "input"))
      (node (ref "SW10") (pin "3") (pinfunction "3_3") (pintype "input"))
      (node (ref "U27") (pin "3") (pinfunction "3_3") (pintype "input"))
    )
    (net (code "23") (name "/E5+") (class "Default")
      (node (ref "H9") (pin "1") (pinfunction "1_1") (pintype "input"))
      (node (ref "R19") (pin "1") (pinfunction "1_1") (pintype "input"))
      (node (ref "R69") (pin "2") (pinfunction "2_2") (pintype "input"))
      (node (ref "SW11") (pin "3") (pinfunction "3_3") (pintype "input"))
      (node (ref "U28") (pin "3") (pinfunction "3_3") (pintype "input"))
    )
    (net (code "24") (name "/E6+") (class "Default")
      (node (ref "H11") (pin "1") (pinfunction "1_1") (pintype "input"))
      (node (ref "R20") (pin "1") (pinfunction "1_1") (pintype "input"))
      (node (ref "R71") (pin "2") (pinfunction "2_2") (pintype "input"))
      (node (ref "SW12") (pin "3") (pinfunction "3_3") (pintype "input"))
      (node (ref "U29") (pin "3") (pinfunction "3_3") (pintype "input"))
    )
    (net (code "25") (name "/SCK") (class "Default")
      (node (ref "H18") (pin "2") (pinfunction "2_2") (pintype "input"))
      (node (ref "U30") (pin "3") (pinfunction "3_3") (pintype "input"))
    )
    (net (code "26") (name "/SCK2") (class "Default")
      (node (ref "H19") (pin "2") (pinfunction "2_2") (pintype "input"))
      (node (ref "U31") (pin "3") (pinfunction "3_3") (pintype "input"))
    )
    (net (code "27") (name "/SCK3") (class "Default")
      (node (ref "H20") (pin "2") (pinfunction "2_2") (pintype "input"))
      (node (ref "U32") (pin "3") (pinfunction "3_3") (pintype "input"))
    )
    (net (code "28") (name "/SCK4") (class "Default")
      (node (ref "H21") (pin "2") (pinfunction "2_2") (pintype "input"))
      (node (ref "U33") (pin "3") (pinfunction "3_3") (pintype "input"))
    )
    (net (code "29") (name "/SCK5") (class "Default")
      (node (ref "H22") (pin "2") (pinfunction "2_2") (pintype "input"))
      (node (ref "U34") (pin "3") (pinfunction "3_3") (pintype "input"))
    )
    (net (code "30") (name "/SCK6") (class "Default")
      (node (ref "H23") (pin "2") (pinfunction "2_2") (pintype "input"))
      (node (ref "U35") (pin "3") (pinfunction "3_3") (pintype "input"))
    )
    (net (code "31") (name "/VCC1") (class "Default")
      (node (ref "H18") (pin "1") (pinfunction "1_1") (pintype "input"))
      (node (ref "U30") (pin "4") (pinfunction "4_4") (pintype "input"))
    )
    (net (code "32") (name "/VCC2") (class "Default")
      (node (ref "H19") (pin "1") (pinfunction "1_1") (pintype "input"))
      (node (ref "U31") (pin "4") (pinfunction "4_4") (pintype "input"))
    )
    (net (code "33") (name "/VCC3") (class "Default")
      (node (ref "H20") (pin "1") (pinfunction "1_1") (pintype "input"))
      (node (ref "U32") (pin "4") (pinfunction "4_4") (pintype "input"))
    )
    (net (code "34") (name "/VCC4") (class "Default")
      (node (ref "H21") (pin "1") (pinfunction "1_1") (pintype "input"))
      (node (ref "U33") (pin "4") (pinfunction "4_4") (pintype "input"))
    )
    (net (code "35") (name "/VCC5") (class "Default")
      (node (ref "H22") (pin "1") (pinfunction "1_1") (pintype "input"))
      (node (ref "U34") (pin "4") (pinfunction "4_4") (pintype "input"))
    )
    (net (code "36") (name "/VCC6") (class "Default")
      (node (ref "H23") (pin "1") (pinfunction "1_1") (pintype "input"))
      (node (ref "U35") (pin "4") (pinfunction "4_4") (pintype "input"))
    )
    (net (code "37") (name "3.3V") (class "Default")
      (node (ref "C3") (pin "2") (pinfunction "2_2") (pintype "input"))
      (node (ref "C7") (pin "2") (pinfunction "2_2") (pintype "input"))
      (node (ref "H25") (pin "2") (pinfunction "2_2") (pintype "input"))
      (node (ref "U1") (pin "2") (pinfunction "VOUT_2") (pintype "input"))
      (node (ref "U1") (pin "4") (pinfunction "VOUT_4") (pintype "input"))
    )
    (net (code "38") (name "5V") (class "Default")
      (node (ref "C8") (pin "2") (pinfunction "2_2") (pintype "input"))
      (node (ref "D1") (pin "1") (pinfunction "C_1") (pintype "input"))
      (node (ref "H26") (pin "2") (pinfunction "2_2") (pintype "input"))
      (node (ref "R14") (pin "1") (pinfunction "1_1") (pintype "input"))
      (node (ref "SW10") (pin "2") (pinfunction "2_2") (pintype "input"))
      (node (ref "SW11") (pin "2") (pinfunction "2_2") (pintype "input"))
      (node (ref "SW12") (pin "2") (pinfunction "2_2") (pintype "input"))
      (node (ref "SW7") (pin "2") (pinfunction "2_2") (pintype "input"))
      (node (ref "SW8") (pin "2") (pinfunction "2_2") (pintype "input"))
      (node (ref "SW9") (pin "2") (pinfunction "2_2") (pintype "input"))
      (node (ref "U1") (pin "3") (pinfunction "VIN_3") (pintype "input"))
      (node (ref "U36") (pin "1") (pinfunction "1_1") (pintype "input"))
    )
    (net (code "39") (name "GND") (class "Default")
      (node (ref "C3") (pin "1") (pinfunction "1_1") (pintype "input"))
      (node (ref "C7") (pin "1") (pinfunction "1_1") (pintype "input"))
      (node (ref "C8") (pin "1") (pinfunction "1_1") (pintype "input"))
      (node (ref "D1") (pin "2") (pinfunction "A_2") (pintype "input"))
      (node (ref "H1") (pin "2") (pinfunction "2_2") (pintype "input"))
      (node (ref "H11") (pin "2") (pinfunction "2_2") (pintype "input"))
      (node (ref "H18") (pin "4") (pinfunction "4_4") (pintype "input"))
      (node (ref "H19") (pin "4") (pinfunction "4_4") (pintype "input"))
      (node (ref "H20") (pin "4") (pinfunction "4_4") (pintype "input"))
      (node (ref "H21") (pin "4") (pinfunction "4_4") (pintype "input"))
      (node (ref "H22") (pin "4") (pinfunction "4_4") (pintype "input"))
      (node (ref "H23") (pin "4") (pinfunction "4_4") (pintype "input"))
      (node (ref "H27") (pin "1") (pinfunction "1_1") (pintype "input"))
      (node (ref "H27") (pin "2") (pinfunction "2_2") (pintype "input"))
      (node (ref "H3") (pin "2") (pinfunction "2_2") (pintype "input"))
      (node (ref "H5") (pin "2") (pinfunction "2_2") (pintype "input"))
      (node (ref "H7") (pin "2") (pinfunction "2_2") (pintype "input"))
      (node (ref "H9") (pin "2") (pinfunction "2_2") (pintype "input"))
      (node (ref "LED10") (pin "2") (pinfunction "-_2") (pintype "input"))
      (node (ref "LED11") (pin "2") (pinfunction "-_2") (pintype "input"))
      (node (ref "LED12") (pin "2") (pinfunction "-_2") (pintype "input"))
      (node (ref "LED13") (pin "2") (pinfunction "-_2") (pintype "input"))
      (node (ref "LED14") (pin "2") (pinfunction "-_2") (pintype "input"))
      (node (ref "LED2") (pin "2") (pinfunction "-_2") (pintype "input"))
      (node (ref "LED3") (pin "1") (pinfunction "-_1") (pintype "input"))
      (node (ref "LED4") (pin "1") (pinfunction "-_1") (pintype "input"))
      (node (ref "LED5") (pin "1") (pinfunction "-_1") (pintype "input"))
      (node (ref "LED6") (pin "1") (pinfunction "-_1") (pintype "input"))
      (node (ref "LED7") (pin "1") (pinfunction "-_1") (pintype "input"))
      (node (ref "LED8") (pin "1") (pinfunction "-_1") (pintype "input"))
      (node (ref "LED9") (pin "2") (pinfunction "-_2") (pintype "input"))
      (node (ref "R62") (pin "1") (pinfunction "1_1") (pintype "input"))
      (node (ref "R64") (pin "1") (pinfunction "1_1") (pintype "input"))
      (node (ref "R66") (pin "1") (pinfunction "1_1") (pintype "input"))
      (node (ref "R68") (pin "1") (pinfunction "1_1") (pintype "input"))
      (node (ref "R70") (pin "1") (pinfunction "1_1") (pintype "input"))
      (node (ref "R72") (pin "1") (pinfunction "1_1") (pintype "input"))
      (node (ref "SW10") (pin "4") (pinfunction "4_4") (pintype "input"))
      (node (ref "SW10") (pin "5") (pinfunction "5_5") (pintype "input"))
      (node (ref "SW11") (pin "4") (pinfunction "4_4") (pintype "input"))
      (node (ref "SW11") (pin "5") (pinfunction "5_5") (pintype "input"))
      (node (ref "SW12") (pin "4") (pinfunction "4_4") (pintype "input"))
      (node (ref "SW12") (pin "5") (pinfunction "5_5") (pintype "input"))
      (node (ref "SW7") (pin "4") (pinfunction "4_4") (pintype "input"))
      (node (ref "SW7") (pin "5") (pinfunction "5_5") (pintype "input"))
      (node (ref "SW8") (pin "4") (pinfunction "4_4") (pintype "input"))
      (node (ref "SW8") (pin "5") (pinfunction "5_5") (pintype "input"))
      (node (ref "SW9") (pin "4") (pinfunction "4_4") (pintype "input"))
      (node (ref "SW9") (pin "5") (pinfunction "5_5") (pintype "input"))
      (node (ref "U1") (pin "1") (pinfunction "GND_1") (pintype "input"))
      (node (ref "U24") (pin "2") (pinfunction "2_2") (pintype "input"))
      (node (ref "U25") (pin "2") (pinfunction "2_2") (pintype "input"))
      (node (ref "U26") (pin "2") (pinfunction "2_2") (pintype "input"))
      (node (ref "U27") (pin "2") (pinfunction "2_2") (pintype "input"))
      (node (ref "U28") (pin "2") (pinfunction "2_2") (pintype "input"))
      (node (ref "U29") (pin "2") (pinfunction "2_2") (pintype "input"))
      (node (ref "U30") (pin "1") (pinfunction "1_1") (pintype "input"))
      (node (ref "U31") (pin "1") (pinfunction "1_1") (pintype "input"))
      (node (ref "U32") (pin "1") (pinfunction "1_1") (pintype "input"))
      (node (ref "U33") (pin "1") (pinfunction "1_1") (pintype "input"))
      (node (ref "U34") (pin "1") (pinfunction "1_1") (pintype "input"))
      (node (ref "U35") (pin "1") (pinfunction "1_1") (pintype "input"))
      (node (ref "U36") (pin "2") (pinfunction "2_2") (pintype "input"))
    )
    (net (code "40") (name "Net-(LED2-+)") (class "Default")
      (node (ref "LED2") (pin "1") (pinfunction "+_1") (pintype "input"))
      (node (ref "R14") (pin "2") (pinfunction "2_2") (pintype "input"))
    )
    (net (code "41") (name "Net-(LED3-+)") (class "Default")
      (node (ref "LED3") (pin "2") (pinfunction "+_2") (pintype "input"))
      (node (ref "R15") (pin "2") (pinfunction "2_2") (pintype "input"))
    )
    (net (code "42") (name "Net-(LED4-+)") (class "Default")
      (node (ref "LED4") (pin "2") (pinfunction "+_2") (pintype "input"))
      (node (ref "R16") (pin "2") (pinfunction "2_2") (pintype "input"))
    )
    (net (code "43") (name "Net-(LED5-+)") (class "Default")
      (node (ref "LED5") (pin "2") (pinfunction "+_2") (pintype "input"))
      (node (ref "R17") (pin "2") (pinfunction "2_2") (pintype "input"))
    )
    (net (code "44") (name "Net-(LED6-+)") (class "Default")
      (node (ref "LED6") (pin "2") (pinfunction "+_2") (pintype "input"))
      (node (ref "R18") (pin "2") (pinfunction "2_2") (pintype "input"))
    )
    (net (code "45") (name "Net-(LED7-+)") (class "Default")
      (node (ref "LED7") (pin "2") (pinfunction "+_2") (pintype "input"))
      (node (ref "R19") (pin "2") (pinfunction "2_2") (pintype "input"))
    )
    (net (code "46") (name "Net-(LED8-+)") (class "Default")
      (node (ref "LED8") (pin "2") (pinfunction "+_2") (pintype "input"))
      (node (ref "R20") (pin "2") (pinfunction "2_2") (pintype "input"))
    )
    (net (code "47") (name "Net-(LED9-+)") (class "Default")
      (node (ref "LED9") (pin "1") (pinfunction "+_1") (pintype "input"))
      (node (ref "R73") (pin "2") (pinfunction "2_2") (pintype "input"))
    )
    (net (code "48") (name "Net-(LED10-+)") (class "Default")
      (node (ref "LED10") (pin "1") (pinfunction "+_1") (pintype "input"))
      (node (ref "R22") (pin "2") (pinfunction "2_2") (pintype "input"))
    )
    (net (code "49") (name "Net-(LED11-+)") (class "Default")
      (node (ref "LED11") (pin "1") (pinfunction "+_1") (pintype "input"))
      (node (ref "R23") (pin "2") (pinfunction "2_2") (pintype "input"))
    )
    (net (code "50") (name "Net-(LED12-+)") (class "Default")
      (node (ref "LED12") (pin "1") (pinfunction "+_1") (pintype "input"))
      (node (ref "R24") (pin "2") (pinfunction "2_2") (pintype "input"))
    )
    (net (code "51") (name "Net-(LED13-+)") (class "Default")
      (node (ref "LED13") (pin "1") (pinfunction "+_1") (pintype "input"))
      (node (ref "R25") (pin "2") (pinfunction "2_2") (pintype "input"))
    )
    (net (code "52") (name "Net-(LED14-+)") (class "Default")
      (node (ref "LED14") (pin "1") (pinfunction "+_1") (pintype "input"))
      (node (ref "R26") (pin "2") (pinfunction "2_2") (pintype "input"))
    )
    (net (code "53") (name "Net-(R22-Pad1)") (class "Default")
      (node (ref "R22") (pin "1") (pinfunction "1_1") (pintype "input"))
      (node (ref "SW8") (pin "1") (pinfunction "1_1") (pintype "input"))
    )
    (net (code "54") (name "Net-(R23-Pad1)") (class "Default")
      (node (ref "R23") (pin "1") (pinfunction "1_1") (pintype "input"))
      (node (ref "SW9") (pin "1") (pinfunction "1_1") (pintype "input"))
    )
    (net (code "55") (name "Net-(R24-Pad1)") (class "Default")
      (node (ref "R24") (pin "1") (pinfunction "1_1") (pintype "input"))
      (node (ref "SW10") (pin "1") (pinfunction "1_1") (pintype "input"))
    )
    (net (code "56") (name "Net-(R25-Pad1)") (class "Default")
      (node (ref "R25") (pin "1") (pinfunction "1_1") (pintype "input"))
      (node (ref "SW11") (pin "1") (pinfunction "1_1") (pintype "input"))
    )
    (net (code "57") (name "Net-(R26-Pad1)") (class "Default")
      (node (ref "R26") (pin "1") (pinfunction "1_1") (pintype "input"))
      (node (ref "SW12") (pin "1") (pinfunction "1_1") (pintype "input"))
    )
    (net (code "58") (name "Net-(R73-Pad1)") (class "Default")
      (node (ref "R73") (pin "1") (pinfunction "1_1") (pintype "input"))
      (node (ref "SW7") (pin "1") (pinfunction "1_1") (pintype "input"))
    )
    (net (code "59") (name "unconnected-(H1-Pad5)") (class "Default")
      (node (ref "H1") (pin "5") (pinfunction "5_5") (pintype "input"))
    )
    (net (code "60") (name "unconnected-(H1-Pad6)") (class "Default")
      (node (ref "H1") (pin "6") (pinfunction "6_6") (pintype "input"))
    )
    (net (code "61") (name "unconnected-(H3-Pad5)") (class "Default")
      (node (ref "H3") (pin "5") (pinfunction "5_5") (pintype "input"))
    )
    (net (code "62") (name "unconnected-(H3-Pad6)") (class "Default")
      (node (ref "H3") (pin "6") (pinfunction "6_6") (pintype "input"))
    )
    (net (code "63") (name "unconnected-(H5-Pad5)") (class "Default")
      (node (ref "H5") (pin "5") (pinfunction "5_5") (pintype "input"))
    )
    (net (code "64") (name "unconnected-(H5-Pad6)") (class "Default")
      (node (ref "H5") (pin "6") (pinfunction "6_6") (pintype "input"))
    )
    (net (code "65") (name "unconnected-(H7-Pad5)") (class "Default")
      (node (ref "H7") (pin "5") (pinfunction "5_5") (pintype "input"))
    )
    (net (code "66") (name "unconnected-(H7-Pad6)") (class "Default")
      (node (ref "H7") (pin "6") (pinfunction "6_6") (pintype "input"))
    )
    (net (code "67") (name "unconnected-(H9-Pad5)") (class "Default")
      (node (ref "H9") (pin "5") (pinfunction "5_5") (pintype "input"))
    )
    (net (code "68") (name "unconnected-(H9-Pad6)") (class "Default")
      (node (ref "H9") (pin "6") (pinfunction "6_6") (pintype "input"))
    )
    (net (code "69") (name "unconnected-(H11-Pad5)") (class "Default")
      (node (ref "H11") (pin "5") (pinfunction "5_5") (pintype "input"))
    )
    (net (code "70") (name "unconnected-(H11-Pad6)") (class "Default")
      (node (ref "H11") (pin "6") (pinfunction "6_6") (pintype "input"))
    )
    (net (code "71") (name "unconnected-(H25-Pad1)") (class "Default")
      (node (ref "H25") (pin "1") (pinfunction "1_1") (pintype "input"))
    )
    (net (code "72") (name "unconnected-(H26-Pad1)") (class "Default")
      (node (ref "H26") (pin "1") (pinfunction "1_1") (pintype "input"))
    )
  )
)
